# 06_ZYNQ_POWER.net
KiCad netlist of a schematic drawn in Altium Designer
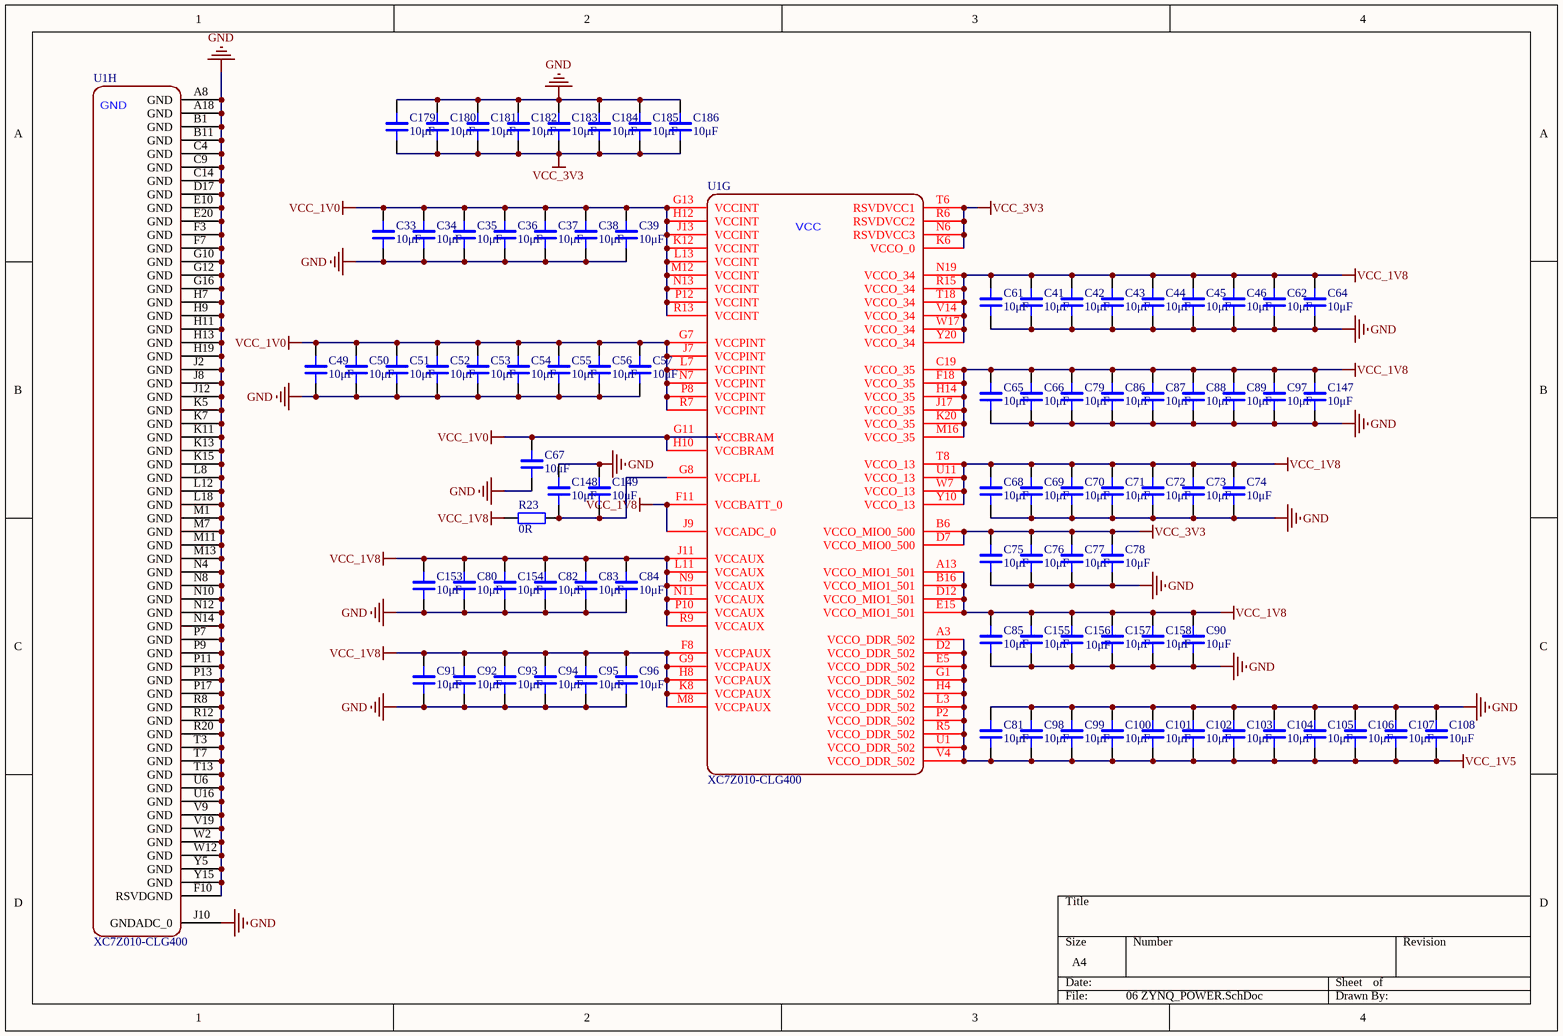
[diagram p0: 06 ZYNQ_POWER.SchDoc]

(export (version "E")
  (design (tool "Eeschema 10.0.6"))
  (components
    (comp (ref "C33")
      (value "10μF")
      (footprint "LC-0402_C")
      (description "Capacitor")
      (libsource (lib "NGFF_M_Key_xc7z010-clg400") (part "CAP_3"))
    )
    (comp (ref "C34")
      (value "10μF")
      (footprint "LC-0402_C")
      (description "Capacitor")
      (libsource (lib "NGFF_M_Key_xc7z010-clg400") (part "CAP_3"))
    )
    (comp (ref "C35")
      (value "10μF")
      (footprint "LC-0402_C")
      (description "Capacitor")
      (libsource (lib "NGFF_M_Key_xc7z010-clg400") (part "CAP_3"))
    )
    (comp (ref "C36")
      (value "10μF")
      (footprint "LC-0402_C")
      (description "Capacitor")
      (libsource (lib "NGFF_M_Key_xc7z010-clg400") (part "CAP_3"))
    )
    (comp (ref "C37")
      (value "10μF")
      (footprint "LC-0402_C")
      (description "Capacitor")
      (libsource (lib "NGFF_M_Key_xc7z010-clg400") (part "CAP_3"))
    )
    (comp (ref "C38")
      (value "10μF")
      (footprint "LC-0402_C")
      (description "Capacitor")
      (libsource (lib "NGFF_M_Key_xc7z010-clg400") (part "CAP_3"))
    )
    (comp (ref "C39")
      (value "10μF")
      (footprint "LC-0402_C")
      (description "Capacitor")
      (libsource (lib "NGFF_M_Key_xc7z010-clg400") (part "CAP_3"))
    )
    (comp (ref "C41")
      (value "10μF")
      (footprint "LC-0402_C")
      (description "Capacitor")
      (libsource (lib "NGFF_M_Key_xc7z010-clg400") (part "CAP_3"))
    )
    (comp (ref "C42")
      (value "10μF")
      (footprint "LC-0402_C")
      (description "Capacitor")
      (libsource (lib "NGFF_M_Key_xc7z010-clg400") (part "CAP_3"))
    )
    (comp (ref "C43")
      (value "10μF")
      (footprint "LC-0402_C")
      (description "Capacitor")
      (libsource (lib "NGFF_M_Key_xc7z010-clg400") (part "CAP_3"))
    )
    (comp (ref "C44")
      (value "10μF")
      (footprint "LC-0402_C")
      (description "Capacitor")
      (libsource (lib "NGFF_M_Key_xc7z010-clg400") (part "CAP_3"))
    )
    (comp (ref "C45")
      (value "10μF")
      (footprint "LC-0402_C")
      (description "Capacitor")
      (libsource (lib "NGFF_M_Key_xc7z010-clg400") (part "CAP_3"))
    )
    (comp (ref "C46")
      (value "10μF")
      (footprint "LC-0402_C")
      (description "Capacitor")
      (libsource (lib "NGFF_M_Key_xc7z010-clg400") (part "CAP_3"))
    )
    (comp (ref "C49")
      (value "10μF")
      (footprint "LC-0402_C")
      (description "Capacitor")
      (libsource (lib "NGFF_M_Key_xc7z010-clg400") (part "CAP_3"))
    )
    (comp (ref "C50")
      (value "10μF")
      (footprint "LC-0402_C")
      (description "Capacitor")
      (libsource (lib "NGFF_M_Key_xc7z010-clg400") (part "CAP_3"))
    )
    (comp (ref "C51")
      (value "10μF")
      (footprint "LC-0402_C")
      (description "Capacitor")
      (libsource (lib "NGFF_M_Key_xc7z010-clg400") (part "CAP_3"))
    )
    (comp (ref "C52")
      (value "10μF")
      (footprint "LC-0402_C")
      (description "Capacitor")
      (libsource (lib "NGFF_M_Key_xc7z010-clg400") (part "CAP_3"))
    )
    (comp (ref "C53")
      (value "10μF")
      (footprint "LC-0402_C")
      (description "Capacitor")
      (libsource (lib "NGFF_M_Key_xc7z010-clg400") (part "CAP_3"))
    )
    (comp (ref "C54")
      (value "10μF")
      (footprint "LC-0402_C")
      (description "Capacitor")
      (libsource (lib "NGFF_M_Key_xc7z010-clg400") (part "CAP_3"))
    )
    (comp (ref "C55")
      (value "10μF")
      (footprint "LC-0402_C")
      (description "Capacitor")
      (libsource (lib "NGFF_M_Key_xc7z010-clg400") (part "CAP_3"))
    )
    (comp (ref "C56")
      (value "10μF")
      (footprint "LC-0402_C")
      (description "Capacitor")
      (libsource (lib "NGFF_M_Key_xc7z010-clg400") (part "CAP_3"))
    )
    (comp (ref "C57")
      (value "10μF")
      (footprint "LC-0402_C")
      (description "Capacitor")
      (libsource (lib "NGFF_M_Key_xc7z010-clg400") (part "CAP_3"))
    )
    (comp (ref "C61")
      (value "10μF")
      (footprint "LC-0402_C")
      (description "Capacitor")
      (libsource (lib "NGFF_M_Key_xc7z010-clg400") (part "CAP_3"))
    )
    (comp (ref "C62")
      (value "10μF")
      (footprint "LC-0402_C")
      (description "Capacitor")
      (libsource (lib "NGFF_M_Key_xc7z010-clg400") (part "CAP_3"))
    )
    (comp (ref "C64")
      (value "10μF")
      (footprint "LC-0402_C")
      (description "Capacitor")
      (libsource (lib "NGFF_M_Key_xc7z010-clg400") (part "CAP_3"))
    )
    (comp (ref "C65")
      (value "10μF")
      (footprint "LC-0402_C")
      (description "Capacitor")
      (libsource (lib "NGFF_M_Key_xc7z010-clg400") (part "CAP_3"))
    )
    (comp (ref "C66")
      (value "10μF")
      (footprint "LC-0402_C")
      (description "Capacitor")
      (libsource (lib "NGFF_M_Key_xc7z010-clg400") (part "CAP_3"))
    )
    (comp (ref "C67")
      (value "10μF")
      (footprint "LC-0402_C")
      (description "Capacitor")
      (libsource (lib "NGFF_M_Key_xc7z010-clg400") (part "CAP_3"))
    )
    (comp (ref "C68")
      (value "10μF")
      (footprint "LC-0402_C")
      (description "Capacitor")
      (libsource (lib "NGFF_M_Key_xc7z010-clg400") (part "CAP_3"))
    )
    (comp (ref "C69")
      (value "10μF")
      (footprint "LC-0402_C")
      (description "Capacitor")
      (libsource (lib "NGFF_M_Key_xc7z010-clg400") (part "CAP_3"))
    )
    (comp (ref "C70")
      (value "10μF")
      (footprint "LC-0402_C")
      (description "Capacitor")
      (libsource (lib "NGFF_M_Key_xc7z010-clg400") (part "CAP_3"))
    )
    (comp (ref "C71")
      (value "10μF")
      (footprint "LC-0402_C")
      (description "Capacitor")
      (libsource (lib "NGFF_M_Key_xc7z010-clg400") (part "CAP_3"))
    )
    (comp (ref "C72")
      (value "10μF")
      (footprint "LC-0402_C")
      (description "Capacitor")
      (libsource (lib "NGFF_M_Key_xc7z010-clg400") (part "CAP_3"))
    )
    (comp (ref "C73")
      (value "10μF")
      (footprint "LC-0402_C")
      (description "Capacitor")
      (libsource (lib "NGFF_M_Key_xc7z010-clg400") (part "CAP_3"))
    )
    (comp (ref "C74")
      (value "10μF")
      (footprint "LC-0402_C")
      (description "Capacitor")
      (libsource (lib "NGFF_M_Key_xc7z010-clg400") (part "CAP_3"))
    )
    (comp (ref "C75")
      (value "10μF")
      (footprint "LC-0402_C")
      (description "Capacitor")
      (libsource (lib "NGFF_M_Key_xc7z010-clg400") (part "CAP_3"))
    )
    (comp (ref "C76")
      (value "10μF")
      (footprint "LC-0402_C")
      (description "Capacitor")
      (libsource (lib "NGFF_M_Key_xc7z010-clg400") (part "CAP_3"))
    )
    (comp (ref "C77")
      (value "10μF")
      (footprint "LC-0402_C")
      (description "Capacitor")
      (libsource (lib "NGFF_M_Key_xc7z010-clg400") (part "CAP_3"))
    )
    (comp (ref "C78")
      (value "10μF")
      (footprint "LC-0402_C")
      (description "Capacitor")
      (libsource (lib "NGFF_M_Key_xc7z010-clg400") (part "CAP_3"))
    )
    (comp (ref "C79")
      (value "10μF")
      (footprint "LC-0402_C")
      (description "Capacitor")
      (libsource (lib "NGFF_M_Key_xc7z010-clg400") (part "CAP_3"))
    )
    (comp (ref "C80")
      (value "10μF")
      (footprint "LC-0402_C")
      (description "Capacitor")
      (libsource (lib "NGFF_M_Key_xc7z010-clg400") (part "CAP_3"))
    )
    (comp (ref "C81")
      (value "10μF")
      (footprint "LC-0402_C")
      (description "Capacitor")
      (libsource (lib "NGFF_M_Key_xc7z010-clg400") (part "CAP_3"))
    )
    (comp (ref "C82")
      (value "10μF")
      (footprint "LC-0402_C")
      (description "Capacitor")
      (libsource (lib "NGFF_M_Key_xc7z010-clg400") (part "CAP_3"))
    )
    (comp (ref "C83")
      (value "10μF")
      (footprint "LC-0402_C")
      (description "Capacitor")
      (libsource (lib "NGFF_M_Key_xc7z010-clg400") (part "CAP_3"))
    )
    (comp (ref "C84")
      (value "10μF")
      (footprint "LC-0402_C")
      (description "Capacitor")
      (libsource (lib "NGFF_M_Key_xc7z010-clg400") (part "CAP_3"))
    )
    (comp (ref "C85")
      (value "10μF")
      (footprint "LC-0402_C")
      (description "Capacitor")
      (libsource (lib "NGFF_M_Key_xc7z010-clg400") (part "CAP_3"))
    )
    (comp (ref "C86")
      (value "10μF")
      (footprint "LC-0402_C")
      (description "Capacitor")
      (libsource (lib "NGFF_M_Key_xc7z010-clg400") (part "CAP_3"))
    )
    (comp (ref "C87")
      (value "10μF")
      (footprint "LC-0402_C")
      (description "Capacitor")
      (libsource (lib "NGFF_M_Key_xc7z010-clg400") (part "CAP_3"))
    )
    (comp (ref "C88")
      (value "10μF")
      (footprint "LC-0402_C")
      (description "Capacitor")
      (libsource (lib "NGFF_M_Key_xc7z010-clg400") (part "CAP_3"))
    )
    (comp (ref "C89")
      (value "10μF")
      (footprint "LC-0402_C")
      (description "Capacitor")
      (libsource (lib "NGFF_M_Key_xc7z010-clg400") (part "CAP_3"))
    )
    (comp (ref "C90")
      (value "10μF")
      (footprint "LC-0402_C")
      (description "Capacitor")
      (libsource (lib "NGFF_M_Key_xc7z010-clg400") (part "CAP_3"))
    )
    (comp (ref "C91")
      (value "10μF")
      (footprint "LC-0402_C")
      (description "Capacitor")
      (libsource (lib "NGFF_M_Key_xc7z010-clg400") (part "CAP_3"))
    )
    (comp (ref "C92")
      (value "10μF")
      (footprint "LC-0402_C")
      (description "Capacitor")
      (libsource (lib "NGFF_M_Key_xc7z010-clg400") (part "CAP_3"))
    )
    (comp (ref "C93")
      (value "10μF")
      (footprint "LC-0402_C")
      (description "Capacitor")
      (libsource (lib "NGFF_M_Key_xc7z010-clg400") (part "CAP_3"))
    )
    (comp (ref "C94")
      (value "10μF")
      (footprint "LC-0402_C")
      (description "Capacitor")
      (libsource (lib "NGFF_M_Key_xc7z010-clg400") (part "CAP_3"))
    )
    (comp (ref "C95")
      (value "10μF")
      (footprint "LC-0402_C")
      (description "Capacitor")
      (libsource (lib "NGFF_M_Key_xc7z010-clg400") (part "CAP_3"))
    )
    (comp (ref "C96")
      (value "10μF")
      (footprint "LC-0402_C")
      (description "Capacitor")
      (libsource (lib "NGFF_M_Key_xc7z010-clg400") (part "CAP_3"))
    )
    (comp (ref "C97")
      (value "10μF")
      (footprint "LC-0402_C")
      (description "Capacitor")
      (libsource (lib "NGFF_M_Key_xc7z010-clg400") (part "CAP_3"))
    )
    (comp (ref "C98")
      (value "10μF")
      (footprint "LC-0402_C")
      (description "Capacitor")
      (libsource (lib "NGFF_M_Key_xc7z010-clg400") (part "CAP_3"))
    )
    (comp (ref "C99")
      (value "10μF")
      (footprint "LC-0402_C")
      (description "Capacitor")
      (libsource (lib "NGFF_M_Key_xc7z010-clg400") (part "CAP_3"))
    )
    (comp (ref "C100")
      (value "10μF")
      (footprint "LC-0402_C")
      (description "Capacitor")
      (libsource (lib "NGFF_M_Key_xc7z010-clg400") (part "CAP_3"))
    )
    (comp (ref "C101")
      (value "10μF")
      (footprint "LC-0402_C")
      (description "Capacitor")
      (libsource (lib "NGFF_M_Key_xc7z010-clg400") (part "CAP_3"))
    )
    (comp (ref "C102")
      (value "10μF")
      (footprint "LC-0402_C")
      (description "Capacitor")
      (libsource (lib "NGFF_M_Key_xc7z010-clg400") (part "CAP_3"))
    )
    (comp (ref "C103")
      (value "10μF")
      (footprint "LC-0402_C")
      (description "Capacitor")
      (libsource (lib "NGFF_M_Key_xc7z010-clg400") (part "CAP_3"))
    )
    (comp (ref "C104")
      (value "10μF")
      (footprint "LC-0402_C")
      (description "Capacitor")
      (libsource (lib "NGFF_M_Key_xc7z010-clg400") (part "CAP_3"))
    )
    (comp (ref "C105")
      (value "10μF")
      (footprint "LC-0402_C")
      (description "Capacitor")
      (libsource (lib "NGFF_M_Key_xc7z010-clg400") (part "CAP_3"))
    )
    (comp (ref "C106")
      (value "10μF")
      (footprint "LC-0402_C")
      (description "Capacitor")
      (libsource (lib "NGFF_M_Key_xc7z010-clg400") (part "CAP_3"))
    )
    (comp (ref "C107")
      (value "10μF")
      (footprint "LC-0402_C")
      (description "Capacitor")
      (libsource (lib "NGFF_M_Key_xc7z010-clg400") (part "CAP_3"))
    )
    (comp (ref "C108")
      (value "10μF")
      (footprint "LC-0402_C")
      (description "Capacitor")
      (libsource (lib "NGFF_M_Key_xc7z010-clg400") (part "CAP_3"))
    )
    (comp (ref "C147")
      (value "10μF")
      (footprint "LC-0402_C")
      (description "Capacitor")
      (libsource (lib "NGFF_M_Key_xc7z010-clg400") (part "CAP_3"))
    )
    (comp (ref "C148")
      (value "10μF")
      (footprint "LC-0402_C")
      (description "Capacitor")
      (libsource (lib "NGFF_M_Key_xc7z010-clg400") (part "CAP_3"))
    )
    (comp (ref "C149")
      (value "10μF")
      (footprint "LC-0402_C")
      (description "Capacitor")
      (libsource (lib "NGFF_M_Key_xc7z010-clg400") (part "CAP_3"))
    )
    (comp (ref "C153")
      (value "10μF")
      (footprint "LC-0402_C")
      (description "Capacitor")
      (libsource (lib "NGFF_M_Key_xc7z010-clg400") (part "CAP_3"))
    )
    (comp (ref "C154")
      (value "10μF")
      (footprint "LC-0402_C")
      (description "Capacitor")
      (libsource (lib "NGFF_M_Key_xc7z010-clg400") (part "CAP_3"))
    )
    (comp (ref "C155")
      (value "10μF")
      (footprint "LC-0402_C")
      (description "Capacitor")
      (libsource (lib "NGFF_M_Key_xc7z010-clg400") (part "CAP_3"))
    )
    (comp (ref "C156")
      (value "10μF")
      (footprint "LC-0402_C")
      (description "Capacitor")
      (libsource (lib "NGFF_M_Key_xc7z010-clg400") (part "CAP_3"))
    )
    (comp (ref "C157")
      (value "10μF")
      (footprint "LC-0402_C")
      (description "Capacitor")
      (libsource (lib "NGFF_M_Key_xc7z010-clg400") (part "CAP_3"))
    )
    (comp (ref "C158")
      (value "10μF")
      (footprint "LC-0402_C")
      (description "Capacitor")
      (libsource (lib "NGFF_M_Key_xc7z010-clg400") (part "CAP_3"))
    )
    (comp (ref "C179")
      (value "10μF")
      (footprint "LC-0402_C")
      (description "Capacitor")
      (libsource (lib "NGFF_M_Key_xc7z010-clg400") (part "CAP_3"))
    )
    (comp (ref "C180")
      (value "10μF")
      (footprint "LC-0402_C")
      (description "Capacitor")
      (libsource (lib "NGFF_M_Key_xc7z010-clg400") (part "CAP_3"))
    )
    (comp (ref "C181")
      (value "10μF")
      (footprint "LC-0402_C")
      (description "Capacitor")
      (libsource (lib "NGFF_M_Key_xc7z010-clg400") (part "CAP_3"))
    )
    (comp (ref "C182")
      (value "10μF")
      (footprint "LC-0402_C")
      (description "Capacitor")
      (libsource (lib "NGFF_M_Key_xc7z010-clg400") (part "CAP_3"))
    )
    (comp (ref "C183")
      (value "10μF")
      (footprint "LC-0402_C")
      (description "Capacitor")
      (libsource (lib "NGFF_M_Key_xc7z010-clg400") (part "CAP_3"))
    )
    (comp (ref "C184")
      (value "10μF")
      (footprint "LC-0402_C")
      (description "Capacitor")
      (libsource (lib "NGFF_M_Key_xc7z010-clg400") (part "CAP_3"))
    )
    (comp (ref "C185")
      (value "10μF")
      (footprint "LC-0402_C")
      (description "Capacitor")
      (libsource (lib "NGFF_M_Key_xc7z010-clg400") (part "CAP_3"))
    )
    (comp (ref "C186")
      (value "10μF")
      (footprint "LC-0402_C")
      (description "Capacitor")
      (libsource (lib "NGFF_M_Key_xc7z010-clg400") (part "CAP_3"))
    )
    (comp (ref "R23")
      (value "0R")
      (footprint "LC-0402_R")
      (description "Resistor")
      (libsource (lib "ZYNQ7010_AD9363") (part "RES"))
    )
    (comp (ref "U1")
      (value "XC7Z010-CLG400")
      (footprint "CLG400-0.8")
      (libsource (lib "DDR3_xc7z010-clg400") (part "XC7Z010-CLG400"))
    )
  )
  (nets
    (net (code "1") (name "GND") (class "Default")
      (node (ref "C100") (pin "2") (pinfunction "2_2") (pintype "passive"))
      (node (ref "C101") (pin "2") (pinfunction "2_2") (pintype "passive"))
      (node (ref "C102") (pin "2") (pinfunction "2_2") (pintype "passive"))
      (node (ref "C103") (pin "2") (pinfunction "2_2") (pintype "passive"))
      (node (ref "C104") (pin "2") (pinfunction "2_2") (pintype "passive"))
      (node (ref "C105") (pin "2") (pinfunction "2_2") (pintype "passive"))
      (node (ref "C106") (pin "2") (pinfunction "2_2") (pintype "passive"))
      (node (ref "C107") (pin "2") (pinfunction "2_2") (pintype "passive"))
      (node (ref "C108") (pin "2") (pinfunction "2_2") (pintype "passive"))
      (node (ref "C147") (pin "1") (pinfunction "1_1") (pintype "passive"))
      (node (ref "C148") (pin "2") (pinfunction "2_2") (pintype "passive"))
      (node (ref "C149") (pin "2") (pinfunction "2_2") (pintype "passive"))
      (node (ref "C153") (pin "1") (pinfunction "1_1") (pintype "passive"))
      (node (ref "C154") (pin "1") (pinfunction "1_1") (pintype "passive"))
      (node (ref "C155") (pin "1") (pinfunction "1_1") (pintype "passive"))
      (node (ref "C156") (pin "1") (pinfunction "1_1") (pintype "passive"))
      (node (ref "C157") (pin "1") (pinfunction "1_1") (pintype "passive"))
      (node (ref "C158") (pin "1") (pinfunction "1_1") (pintype "passive"))
      (node (ref "C179") (pin "2") (pinfunction "2_2") (pintype "passive"))
      (node (ref "C180") (pin "2") (pinfunction "2_2") (pintype "passive"))
      (node (ref "C181") (pin "2") (pinfunction "2_2") (pintype "passive"))
      (node (ref "C182") (pin "2") (pinfunction "2_2") (pintype "passive"))
      (node (ref "C183") (pin "2") (pinfunction "2_2") (pintype "passive"))
      (node (ref "C184") (pin "2") (pinfunction "2_2") (pintype "passive"))
      (node (ref "C185") (pin "2") (pinfunction "2_2") (pintype "passive"))
      (node (ref "C186") (pin "2") (pinfunction "2_2") (pintype "passive"))
      (node (ref "C33") (pin "1") (pinfunction "1_1") (pintype "passive"))
      (node (ref "C34") (pin "1") (pinfunction "1_1") (pintype "passive"))
      (node (ref "C35") (pin "1") (pinfunction "1_1") (pintype "passive"))
      (node (ref "C36") (pin "1") (pinfunction "1_1") (pintype "passive"))
      (node (ref "C37") (pin "1") (pinfunction "1_1") (pintype "passive"))
      (node (ref "C38") (pin "1") (pinfunction "1_1") (pintype "passive"))
      (node (ref "C39") (pin "1") (pinfunction "1_1") (pintype "passive"))
      (node (ref "C41") (pin "1") (pinfunction "1_1") (pintype "passive"))
      (node (ref "C42") (pin "1") (pinfunction "1_1") (pintype "passive"))
      (node (ref "C43") (pin "1") (pinfunction "1_1") (pintype "passive"))
      (node (ref "C44") (pin "1") (pinfunction "1_1") (pintype "passive"))
      (node (ref "C45") (pin "1") (pinfunction "1_1") (pintype "passive"))
      (node (ref "C46") (pin "1") (pinfunction "1_1") (pintype "passive"))
      (node (ref "C49") (pin "1") (pinfunction "1_1") (pintype "passive"))
      (node (ref "C50") (pin "1") (pinfunction "1_1") (pintype "passive"))
      (node (ref "C51") (pin "1") (pinfunction "1_1") (pintype "passive"))
      (node (ref "C52") (pin "1") (pinfunction "1_1") (pintype "passive"))
      (node (ref "C53") (pin "1") (pinfunction "1_1") (pintype "passive"))
      (node (ref "C54") (pin "1") (pinfunction "1_1") (pintype "passive"))
      (node (ref "C55") (pin "1") (pinfunction "1_1") (pintype "passive"))
      (node (ref "C56") (pin "1") (pinfunction "1_1") (pintype "passive"))
      (node (ref "C57") (pin "1") (pinfunction "1_1") (pintype "passive"))
      (node (ref "C61") (pin "1") (pinfunction "1_1") (pintype "passive"))
      (node (ref "C62") (pin "1") (pinfunction "1_1") (pintype "passive"))
      (node (ref "C64") (pin "1") (pinfunction "1_1") (pintype "passive"))
      (node (ref "C65") (pin "1") (pinfunction "1_1") (pintype "passive"))
      (node (ref "C66") (pin "1") (pinfunction "1_1") (pintype "passive"))
      (node (ref "C67") (pin "1") (pinfunction "1_1") (pintype "passive"))
      (node (ref "C68") (pin "1") (pinfunction "1_1") (pintype "passive"))
      (node (ref "C69") (pin "1") (pinfunction "1_1") (pintype "passive"))
      (node (ref "C70") (pin "1") (pinfunction "1_1") (pintype "passive"))
      (node (ref "C71") (pin "1") (pinfunction "1_1") (pintype "passive"))
      (node (ref "C72") (pin "1") (pinfunction "1_1") (pintype "passive"))
      (node (ref "C73") (pin "1") (pinfunction "1_1") (pintype "passive"))
      (node (ref "C74") (pin "1") (pinfunction "1_1") (pintype "passive"))
      (node (ref "C75") (pin "1") (pinfunction "1_1") (pintype "passive"))
      (node (ref "C76") (pin "1") (pinfunction "1_1") (pintype "passive"))
      (node (ref "C77") (pin "1") (pinfunction "1_1") (pintype "passive"))
      (node (ref "C78") (pin "1") (pinfunction "1_1") (pintype "passive"))
      (node (ref "C79") (pin "1") (pinfunction "1_1") (pintype "passive"))
      (node (ref "C80") (pin "1") (pinfunction "1_1") (pintype "passive"))
      (node (ref "C81") (pin "2") (pinfunction "2_2") (pintype "passive"))
      (node (ref "C82") (pin "1") (pinfunction "1_1") (pintype "passive"))
      (node (ref "C83") (pin "1") (pinfunction "1_1") (pintype "passive"))
      (node (ref "C84") (pin "1") (pinfunction "1_1") (pintype "passive"))
      (node (ref "C85") (pin "1") (pinfunction "1_1") (pintype "passive"))
      (node (ref "C86") (pin "1") (pinfunction "1_1") (pintype "passive"))
      (node (ref "C87") (pin "1") (pinfunction "1_1") (pintype "passive"))
      (node (ref "C88") (pin "1") (pinfunction "1_1") (pintype "passive"))
      (node (ref "C89") (pin "1") (pinfunction "1_1") (pintype "passive"))
      (node (ref "C90") (pin "1") (pinfunction "1_1") (pintype "passive"))
      (node (ref "C91") (pin "1") (pinfunction "1_1") (pintype "passive"))
      (node (ref "C92") (pin "1") (pinfunction "1_1") (pintype "passive"))
      (node (ref "C93") (pin "1") (pinfunction "1_1") (pintype "passive"))
      (node (ref "C94") (pin "1") (pinfunction "1_1") (pintype "passive"))
      (node (ref "C95") (pin "1") (pinfunction "1_1") (pintype "passive"))
      (node (ref "C96") (pin "1") (pinfunction "1_1") (pintype "passive"))
      (node (ref "C97") (pin "1") (pinfunction "1_1") (pintype "passive"))
      (node (ref "C98") (pin "2") (pinfunction "2_2") (pintype "passive"))
      (node (ref "C99") (pin "2") (pinfunction "2_2") (pintype "passive"))
      (node (ref "U1") (pin "A18") (pinfunction "GND_A18") (pintype "passive"))
      (node (ref "U1") (pin "A8") (pinfunction "GND_A8") (pintype "passive"))
      (node (ref "U1") (pin "B1") (pinfunction "GND_B1") (pintype "passive"))
      (node (ref "U1") (pin "B11") (pinfunction "GND_B11") (pintype "passive"))
      (node (ref "U1") (pin "C14") (pinfunction "GND_C14") (pintype "passive"))
      (node (ref "U1") (pin "C4") (pinfunction "GND_C4") (pintype "passive"))
      (node (ref "U1") (pin "C9") (pinfunction "GND_C9") (pintype "passive"))
      (node (ref "U1") (pin "D17") (pinfunction "GND_D17") (pintype "passive"))
      (node (ref "U1") (pin "E10") (pinfunction "GND_E10") (pintype "passive"))
      (node (ref "U1") (pin "E20") (pinfunction "GND_E20") (pintype "passive"))
      (node (ref "U1") (pin "F10") (pinfunction "RSVDGND_F10") (pintype "passive"))
      (node (ref "U1") (pin "F3") (pinfunction "GND_F3") (pintype "passive"))
      (node (ref "U1") (pin "F7") (pinfunction "GND_F7") (pintype "passive"))
      (node (ref "U1") (pin "G10") (pinfunction "GND_G10") (pintype "passive"))
      (node (ref "U1") (pin "G12") (pinfunction "GND_G12") (pintype "passive"))
      (node (ref "U1") (pin "G16") (pinfunction "GND_G16") (pintype "passive"))
      (node (ref "U1") (pin "H11") (pinfunction "GND_H11") (pintype "passive"))
      (node (ref "U1") (pin "H13") (pinfunction "GND_H13") (pintype "passive"))
      (node (ref "U1") (pin "H19") (pinfunction "GND_H19") (pintype "passive"))
      (node (ref "U1") (pin "H7") (pinfunction "GND_H7") (pintype "passive"))
      (node (ref "U1") (pin "H9") (pinfunction "GND_H9") (pintype "passive"))
      (node (ref "U1") (pin "J10") (pinfunction "GNDADC_0_J10") (pintype "passive"))
      (node (ref "U1") (pin "J12") (pinfunction "GND_J12") (pintype "passive"))
      (node (ref "U1") (pin "J2") (pinfunction "GND_J2") (pintype "passive"))
      (node (ref "U1") (pin "J8") (pinfunction "GND_J8") (pintype "passive"))
      (node (ref "U1") (pin "K11") (pinfunction "GND_K11") (pintype "passive"))
      (node (ref "U1") (pin "K13") (pinfunction "GND_K13") (pintype "passive"))
      (node (ref "U1") (pin "K15") (pinfunction "GND_K15") (pintype "passive"))
      (node (ref "U1") (pin "K5") (pinfunction "GND_K5") (pintype "passive"))
      (node (ref "U1") (pin "K7") (pinfunction "GND_K7") (pintype "passive"))
      (node (ref "U1") (pin "L12") (pinfunction "GND_L12") (pintype "passive"))
      (node (ref "U1") (pin "L18") (pinfunction "GND_L18") (pintype "passive"))
      (node (ref "U1") (pin "L8") (pinfunction "GND_L8") (pintype "passive"))
      (node (ref "U1") (pin "M1") (pinfunction "GND_M1") (pintype "passive"))
      (node (ref "U1") (pin "M11") (pinfunction "GND_M11") (pintype "passive"))
      (node (ref "U1") (pin "M13") (pinfunction "GND_M13") (pintype "passive"))
      (node (ref "U1") (pin "M7") (pinfunction "GND_M7") (pintype "passive"))
      (node (ref "U1") (pin "N10") (pinfunction "GND_N10") (pintype "passive"))
      (node (ref "U1") (pin "N12") (pinfunction "GND_N12") (pintype "passive"))
      (node (ref "U1") (pin "N14") (pinfunction "GND_N14") (pintype "passive"))
      (node (ref "U1") (pin "N4") (pinfunction "GND_N4") (pintype "passive"))
      (node (ref "U1") (pin "N8") (pinfunction "GND_N8") (pintype "passive"))
      (node (ref "U1") (pin "P11") (pinfunction "GND_P11") (pintype "passive"))
      (node (ref "U1") (pin "P13") (pinfunction "GND_P13") (pintype "passive"))
      (node (ref "U1") (pin "P17") (pinfunction "GND_P17") (pintype "passive"))
      (node (ref "U1") (pin "P7") (pinfunction "GND_P7") (pintype "passive"))
      (node (ref "U1") (pin "P9") (pinfunction "GND_P9") (pintype "passive"))
      (node (ref "U1") (pin "R12") (pinfunction "GND_R12") (pintype "passive"))
      (node (ref "U1") (pin "R20") (pinfunction "GND_R20") (pintype "passive"))
      (node (ref "U1") (pin "R8") (pinfunction "GND_R8") (pintype "passive"))
      (node (ref "U1") (pin "T13") (pinfunction "GND_T13") (pintype "passive"))
      (node (ref "U1") (pin "T3") (pinfunction "GND_T3") (pintype "passive"))
      (node (ref "U1") (pin "T7") (pinfunction "GND_T7") (pintype "passive"))
      (node (ref "U1") (pin "U16") (pinfunction "GND_U16") (pintype "passive"))
      (node (ref "U1") (pin "U6") (pinfunction "GND_U6") (pintype "passive"))
      (node (ref "U1") (pin "V19") (pinfunction "GND_V19") (pintype "passive"))
      (node (ref "U1") (pin "V9") (pinfunction "GND_V9") (pintype "passive"))
      (node (ref "U1") (pin "W12") (pinfunction "GND_W12") (pintype "passive"))
      (node (ref "U1") (pin "W2") (pinfunction "GND_W2") (pintype "passive"))
      (node (ref "U1") (pin "Y15") (pinfunction "GND_Y15") (pintype "passive"))
      (node (ref "U1") (pin "Y5") (pinfunction "GND_Y5") (pintype "passive"))
    )
    (net (code "2") (name "Net-(U1G-VCCPLL)") (class "Default")
      (node (ref "C148") (pin "1") (pinfunction "1_1") (pintype "passive"))
      (node (ref "C149") (pin "1") (pinfunction "1_1") (pintype "passive"))
      (node (ref "R23") (pin "2") (pinfunction "2_2") (pintype "passive"))
      (node (ref "U1") (pin "G8") (pinfunction "VCCPLL_G8") (pintype "passive"))
    )
    (net (code "3") (name "VCC_1V0") (class "Default")
      (node (ref "C33") (pin "2") (pinfunction "2_2") (pintype "passive"))
      (node (ref "C34") (pin "2") (pinfunction "2_2") (pintype "passive"))
      (node (ref "C35") (pin "2") (pinfunction "2_2") (pintype "passive"))
      (node (ref "C36") (pin "2") (pinfunction "2_2") (pintype "passive"))
      (node (ref "C37") (pin "2") (pinfunction "2_2") (pintype "passive"))
      (node (ref "C38") (pin "2") (pinfunction "2_2") (pintype "passive"))
      (node (ref "C39") (pin "2") (pinfunction "2_2") (pintype "passive"))
      (node (ref "C49") (pin "2") (pinfunction "2_2") (pintype "passive"))
      (node (ref "C50") (pin "2") (pinfunction "2_2") (pintype "passive"))
      (node (ref "C51") (pin "2") (pinfunction "2_2") (pintype "passive"))
      (node (ref "C52") (pin "2") (pinfunction "2_2") (pintype "passive"))
      (node (ref "C53") (pin "2") (pinfunction "2_2") (pintype "passive"))
      (node (ref "C54") (pin "2") (pinfunction "2_2") (pintype "passive"))
      (node (ref "C55") (pin "2") (pinfunction "2_2") (pintype "passive"))
      (node (ref "C56") (pin "2") (pinfunction "2_2") (pintype "passive"))
      (node (ref "C57") (pin "2") (pinfunction "2_2") (pintype "passive"))
      (node (ref "C67") (pin "2") (pinfunction "2_2") (pintype "passive"))
      (node (ref "U1") (pin "G11") (pinfunction "VCCBRAM_G11") (pintype "passive"))
      (node (ref "U1") (pin "G13") (pinfunction "VCCINT_G13") (pintype "passive"))
      (node (ref "U1") (pin "G7") (pinfunction "VCCPINT_G7") (pintype "passive"))
      (node (ref "U1") (pin "H10") (pinfunction "VCCBRAM_H10") (pintype "passive"))
      (node (ref "U1") (pin "H12") (pinfunction "VCCINT_H12") (pintype "passive"))
      (node (ref "U1") (pin "J13") (pinfunction "VCCINT_J13") (pintype "passive"))
      (node (ref "U1") (pin "J7") (pinfunction "VCCPINT_J7") (pintype "passive"))
      (node (ref "U1") (pin "K12") (pinfunction "VCCINT_K12") (pintype "passive"))
      (node (ref "U1") (pin "L13") (pinfunction "VCCINT_L13") (pintype "passive"))
      (node (ref "U1") (pin "L7") (pinfunction "VCCPINT_L7") (pintype "passive"))
      (node (ref "U1") (pin "M12") (pinfunction "VCCINT_M12") (pintype "passive"))
      (node (ref "U1") (pin "N13") (pinfunction "VCCINT_N13") (pintype "passive"))
      (node (ref "U1") (pin "N7") (pinfunction "VCCPINT_N7") (pintype "passive"))
      (node (ref "U1") (pin "P12") (pinfunction "VCCINT_P12") (pintype "passive"))
      (node (ref "U1") (pin "P8") (pinfunction "VCCPINT_P8") (pintype "passive"))
      (node (ref "U1") (pin "R13") (pinfunction "VCCINT_R13") (pintype "passive"))
      (node (ref "U1") (pin "R7") (pinfunction "VCCPINT_R7") (pintype "passive"))
    )
    (net (code "4") (name "VCC_1V5") (class "Default")
      (node (ref "C100") (pin "1") (pinfunction "1_1") (pintype "passive"))
      (node (ref "C101") (pin "1") (pinfunction "1_1") (pintype "passive"))
      (node (ref "C102") (pin "1") (pinfunction "1_1") (pintype "passive"))
      (node (ref "C103") (pin "1") (pinfunction "1_1") (pintype "passive"))
      (node (ref "C104") (pin "1") (pinfunction "1_1") (pintype "passive"))
      (node (ref "C105") (pin "1") (pinfunction "1_1") (pintype "passive"))
      (node (ref "C106") (pin "1") (pinfunction "1_1") (pintype "passive"))
      (node (ref "C107") (pin "1") (pinfunction "1_1") (pintype "passive"))
      (node (ref "C108") (pin "1") (pinfunction "1_1") (pintype "passive"))
      (node (ref "C81") (pin "1") (pinfunction "1_1") (pintype "passive"))
      (node (ref "C98") (pin "1") (pinfunction "1_1") (pintype "passive"))
      (node (ref "C99") (pin "1") (pinfunction "1_1") (pintype "passive"))
      (node (ref "U1") (pin "A3") (pinfunction "VCCO_DDR_502_A3") (pintype "passive"))
      (node (ref "U1") (pin "D2") (pinfunction "VCCO_DDR_502_D2") (pintype "passive"))
      (node (ref "U1") (pin "E5") (pinfunction "VCCO_DDR_502_E5") (pintype "passive"))
      (node (ref "U1") (pin "G1") (pinfunction "VCCO_DDR_502_G1") (pintype "passive"))
      (node (ref "U1") (pin "H4") (pinfunction "VCCO_DDR_502_H4") (pintype "passive"))
      (node (ref "U1") (pin "L3") (pinfunction "VCCO_DDR_502_L3") (pintype "passive"))
      (node (ref "U1") (pin "P2") (pinfunction "VCCO_DDR_502_P2") (pintype "passive"))
      (node (ref "U1") (pin "R5") (pinfunction "VCCO_DDR_502_R5") (pintype "passive"))
      (node (ref "U1") (pin "U1") (pinfunction "VCCO_DDR_502_U1") (pintype "passive"))
      (node (ref "U1") (pin "V4") (pinfunction "VCCO_DDR_502_V4") (pintype "passive"))
    )
    (net (code "5") (name "VCC_1V8") (class "Default")
      (node (ref "C147") (pin "2") (pinfunction "2_2") (pintype "passive"))
      (node (ref "C153") (pin "2") (pinfunction "2_2") (pintype "passive"))
      (node (ref "C154") (pin "2") (pinfunction "2_2") (pintype "passive"))
      (node (ref "C155") (pin "2") (pinfunction "2_2") (pintype "passive"))
      (node (ref "C156") (pin "2") (pinfunction "2_2") (pintype "passive"))
      (node (ref "C157") (pin "2") (pinfunction "2_2") (pintype "passive"))
      (node (ref "C158") (pin "2") (pinfunction "2_2") (pintype "passive"))
      (node (ref "C41") (pin "2") (pinfunction "2_2") (pintype "passive"))
      (node (ref "C42") (pin "2") (pinfunction "2_2") (pintype "passive"))
      (node (ref "C43") (pin "2") (pinfunction "2_2") (pintype "passive"))
      (node (ref "C44") (pin "2") (pinfunction "2_2") (pintype "passive"))
      (node (ref "C45") (pin "2") (pinfunction "2_2") (pintype "passive"))
      (node (ref "C46") (pin "2") (pinfunction "2_2") (pintype "passive"))
      (node (ref "C61") (pin "2") (pinfunction "2_2") (pintype "passive"))
      (node (ref "C62") (pin "2") (pinfunction "2_2") (pintype "passive"))
      (node (ref "C64") (pin "2") (pinfunction "2_2") (pintype "passive"))
      (node (ref "C65") (pin "2") (pinfunction "2_2") (pintype "passive"))
      (node (ref "C66") (pin "2") (pinfunction "2_2") (pintype "passive"))
      (node (ref "C68") (pin "2") (pinfunction "2_2") (pintype "passive"))
      (node (ref "C69") (pin "2") (pinfunction "2_2") (pintype "passive"))
      (node (ref "C70") (pin "2") (pinfunction "2_2") (pintype "passive"))
      (node (ref "C71") (pin "2") (pinfunction "2_2") (pintype "passive"))
      (node (ref "C72") (pin "2") (pinfunction "2_2") (pintype "passive"))
      (node (ref "C73") (pin "2") (pinfunction "2_2") (pintype "passive"))
      (node (ref "C74") (pin "2") (pinfunction "2_2") (pintype "passive"))
      (node (ref "C79") (pin "2") (pinfunction "2_2") (pintype "passive"))
      (node (ref "C80") (pin "2") (pinfunction "2_2") (pintype "passive"))
      (node (ref "C82") (pin "2") (pinfunction "2_2") (pintype "passive"))
      (node (ref "C83") (pin "2") (pinfunction "2_2") (pintype "passive"))
      (node (ref "C84") (pin "2") (pinfunction "2_2") (pintype "passive"))
      (node (ref "C85") (pin "2") (pinfunction "2_2") (pintype "passive"))
      (node (ref "C86") (pin "2") (pinfunction "2_2") (pintype "passive"))
      (node (ref "C87") (pin "2") (pinfunction "2_2") (pintype "passive"))
      (node (ref "C88") (pin "2") (pinfunction "2_2") (pintype "passive"))
      (node (ref "C89") (pin "2") (pinfunction "2_2") (pintype "passive"))
      (node (ref "C90") (pin "2") (pinfunction "2_2") (pintype "passive"))
      (node (ref "C91") (pin "2") (pinfunction "2_2") (pintype "passive"))
      (node (ref "C92") (pin "2") (pinfunction "2_2") (pintype "passive"))
      (node (ref "C93") (pin "2") (pinfunction "2_2") (pintype "passive"))
      (node (ref "C94") (pin "2") (pinfunction "2_2") (pintype "passive"))
      (node (ref "C95") (pin "2") (pinfunction "2_2") (pintype "passive"))
      (node (ref "C96") (pin "2") (pinfunction "2_2") (pintype "passive"))
      (node (ref "C97") (pin "2") (pinfunction "2_2") (pintype "passive"))
      (node (ref "R23") (pin "1") (pinfunction "1_1") (pintype "passive"))
      (node (ref "U1") (pin "A13") (pinfunction "VCCO_MIO1_501_A13") (pintype "passive"))
      (node (ref "U1") (pin "B16") (pinfunction "VCCO_MIO1_501_B16") (pintype "passive"))
      (node (ref "U1") (pin "C19") (pinfunction "VCCO_35_C19") (pintype "passive"))
      (node (ref "U1") (pin "D12") (pinfunction "VCCO_MIO1_501_D12") (pintype "passive"))
      (node (ref "U1") (pin "E15") (pinfunction "VCCO_MIO1_501_E15") (pintype "passive"))
      (node (ref "U1") (pin "F11") (pinfunction "VCCBATT_0_F11") (pintype "passive"))
      (node (ref "U1") (pin "F18") (pinfunction "VCCO_35_F18") (pintype "passive"))
      (node (ref "U1") (pin "F8") (pinfunction "VCCPAUX_F8") (pintype "passive"))
      (node (ref "U1") (pin "G9") (pinfunction "VCCPAUX_G9") (pintype "passive"))
      (node (ref "U1") (pin "H14") (pinfunction "VCCO_35_H14") (pintype "passive"))
      (node (ref "U1") (pin "H8") (pinfunction "VCCPAUX_H8") (pintype "passive"))
      (node (ref "U1") (pin "J11") (pinfunction "VCCAUX_J11") (pintype "passive"))
      (node (ref "U1") (pin "J17") (pinfunction "VCCO_35_J17") (pintype "passive"))
      (node (ref "U1") (pin "J9") (pinfunction "VCCADC_0_J9") (pintype "passive"))
      (node (ref "U1") (pin "K20") (pinfunction "VCCO_35_K20") (pintype "passive"))
      (node (ref "U1") (pin "K8") (pinfunction "VCCPAUX_K8") (pintype "passive"))
      (node (ref "U1") (pin "L11") (pinfunction "VCCAUX_L11") (pintype "passive"))
      (node (ref "U1") (pin "M16") (pinfunction "VCCO_35_M16") (pintype "passive"))
      (node (ref "U1") (pin "M8") (pinfunction "VCCPAUX_M8") (pintype "passive"))
      (node (ref "U1") (pin "N11") (pinfunction "VCCAUX_N11") (pintype "passive"))
      (node (ref "U1") (pin "N19") (pinfunction "VCCO_34_N19") (pintype "passive"))
      (node (ref "U1") (pin "N9") (pinfunction "VCCAUX_N9") (pintype "passive"))
      (node (ref "U1") (pin "P10") (pinfunction "VCCAUX_P10") (pintype "passive"))
      (node (ref "U1") (pin "R15") (pinfunction "VCCO_34_R15") (pintype "passive"))
      (node (ref "U1") (pin "R9") (pinfunction "VCCAUX_R9") (pintype "passive"))
      (node (ref "U1") (pin "T18") (pinfunction "VCCO_34_T18") (pintype "passive"))
      (node (ref "U1") (pin "T8") (pinfunction "VCCO_13_T8") (pintype "passive"))
      (node (ref "U1") (pin "U11") (pinfunction "VCCO_13_U11") (pintype "passive"))
      (node (ref "U1") (pin "V14") (pinfunction "VCCO_34_V14") (pintype "passive"))
      (node (ref "U1") (pin "W17") (pinfunction "VCCO_34_W17") (pintype "passive"))
      (node (ref "U1") (pin "W7") (pinfunction "VCCO_13_W7") (pintype "passive"))
      (node (ref "U1") (pin "Y10") (pinfunction "VCCO_13_Y10") (pintype "passive"))
      (node (ref "U1") (pin "Y20") (pinfunction "VCCO_34_Y20") (pintype "passive"))
    )
    (net (code "6") (name "VCC_3V3") (class "Default")
      (node (ref "C179") (pin "1") (pinfunction "1_1") (pintype "passive"))
      (node (ref "C180") (pin "1") (pinfunction "1_1") (pintype "passive"))
      (node (ref "C181") (pin "1") (pinfunction "1_1") (pintype "passive"))
      (node (ref "C182") (pin "1") (pinfunction "1_1") (pintype "passive"))
      (node (ref "C183") (pin "1") (pinfunction "1_1") (pintype "passive"))
      (node (ref "C184") (pin "1") (pinfunction "1_1") (pintype "passive"))
      (node (ref "C185") (pin "1") (pinfunction "1_1") (pintype "passive"))
      (node (ref "C186") (pin "1") (pinfunction "1_1") (pintype "passive"))
      (node (ref "C75") (pin "2") (pinfunction "2_2") (pintype "passive"))
      (node (ref "C76") (pin "2") (pinfunction "2_2") (pintype "passive"))
      (node (ref "C77") (pin "2") (pinfunction "2_2") (pintype "passive"))
      (node (ref "C78") (pin "2") (pinfunction "2_2") (pintype "passive"))
      (node (ref "U1") (pin "B6") (pinfunction "VCCO_MIO0_500_B6") (pintype "passive"))
      (node (ref "U1") (pin "D7") (pinfunction "VCCO_MIO0_500_D7") (pintype "passive"))
      (node (ref "U1") (pin "K6") (pinfunction "VCCO_0_K6") (pintype "passive"))
      (node (ref "U1") (pin "N6") (pinfunction "RSVDVCC3_N6") (pintype "passive"))
      (node (ref "U1") (pin "R6") (pinfunction "RSVDVCC2_R6") (pintype "passive"))
      (node (ref "U1") (pin "T6") (pinfunction "RSVDVCC1_T6") (pintype "passive"))
    )
  )
)
